# PFC_screen.net
KiCad netlist of a schematic drawn in EAGLE
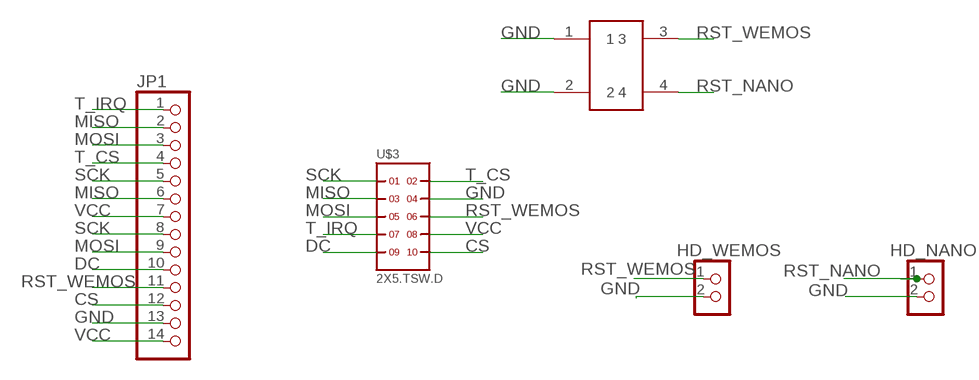
[diagram p0: schematic, sheet 1]

(export (version "E")
  (design (tool "Eeschema 10.0.6"))
  (components
    (comp (ref "HD_NANO")
      (value "PINHD-2X1")
      (footprint "eagle-import:2X01")
      (libsource (lib "eagle-import") (part "PINHD-2X1"))
    )
    (comp (ref "HD_WEMOS")
      (value "PINHD-2X1")
      (footprint "eagle-import:2X01")
      (libsource (lib "eagle-import") (part "PINHD-2X1"))
    )
    (comp (ref "JP1")
      (value "PINHD-1X14-CB")
      (footprint "eagle-import:1X14-CB")
      (libsource (lib "eagle-import") (part "PINHD-1X14-CB"))
    )
    (comp (ref "U$1")
      (value "EK1019")
      (footprint "eagle-import:EK1019_6X6X5MM")
      (libsource (lib "eagle-import") (part "EK1019"))
    )
    (comp (ref "U$3")
      (value "2X5.TSW.D")
      (footprint "eagle-import:TSW-105-XXX-D-XXX")
      (libsource (lib "eagle-import") (part "2X5.TSW.D"))
    )
  )
  (nets
    (net (code "1") (name "/CS") (class "Default")
      (node (ref "JP1") (pin "12") (pinfunction "12_12") (pintype "passive"))
      (node (ref "U$3") (pin "10") (pinfunction "10_10") (pintype "bidirectional"))
    )
    (net (code "2") (name "/DC") (class "Default")
      (node (ref "JP1") (pin "10") (pinfunction "10_10") (pintype "passive"))
      (node (ref "U$3") (pin "9") (pinfunction "9_9") (pintype "bidirectional"))
    )
    (net (code "3") (name "/GND") (class "Default")
      (node (ref "HD_NANO") (pin "2") (pinfunction "3_2") (pintype "passive"))
      (node (ref "HD_WEMOS") (pin "2") (pinfunction "3_2") (pintype "passive"))
      (node (ref "JP1") (pin "13") (pinfunction "13_13") (pintype "passive"))
      (node (ref "U$1") (pin "1") (pinfunction "1_1") (pintype "bidirectional"))
      (node (ref "U$1") (pin "2") (pinfunction "2_2") (pintype "bidirectional"))
      (node (ref "U$3") (pin "4") (pinfunction "4_4") (pintype "bidirectional"))
    )
    (net (code "4") (name "/MISO") (class "Default")
      (node (ref "JP1") (pin "2") (pinfunction "2_2") (pintype "passive"))
      (node (ref "JP1") (pin "6") (pinfunction "6_6") (pintype "passive"))
      (node (ref "U$3") (pin "3") (pinfunction "3_3") (pintype "bidirectional"))
    )
    (net (code "5") (name "/MOSI") (class "Default")
      (node (ref "JP1") (pin "3") (pinfunction "3_3") (pintype "passive"))
      (node (ref "JP1") (pin "9") (pinfunction "9_9") (pintype "passive"))
      (node (ref "U$3") (pin "5") (pinfunction "5_5") (pintype "bidirectional"))
    )
    (net (code "6") (name "/RST_NANO") (class "Default")
      (node (ref "HD_NANO") (pin "1") (pinfunction "1_1") (pintype "passive"))
      (node (ref "U$1") (pin "4") (pinfunction "4_4") (pintype "bidirectional"))
    )
    (net (code "7") (name "/RST_WEMOS") (class "Default")
      (node (ref "HD_WEMOS") (pin "1") (pinfunction "1_1") (pintype "passive"))
      (node (ref "JP1") (pin "11") (pinfunction "11_11") (pintype "passive"))
      (node (ref "U$1") (pin "3") (pinfunction "3_3") (pintype "bidirectional"))
      (node (ref "U$3") (pin "6") (pinfunction "6_6") (pintype "bidirectional"))
    )
    (net (code "8") (name "/SCK") (class "Default")
      (node (ref "JP1") (pin "5") (pinfunction "5_5") (pintype "passive"))
      (node (ref "JP1") (pin "8") (pinfunction "8_8") (pintype "passive"))
      (node (ref "U$3") (pin "1") (pinfunction "1_1") (pintype "bidirectional"))
    )
    (net (code "9") (name "/T_CS") (class "Default")
      (node (ref "JP1") (pin "4") (pinfunction "4_4") (pintype "passive"))
      (node (ref "U$3") (pin "2") (pinfunction "2_2") (pintype "bidirectional"))
    )
    (net (code "10") (name "/T_IRQ") (class "Default")
      (node (ref "JP1") (pin "1") (pinfunction "1_1") (pintype "passive"))
      (node (ref "U$3") (pin "7") (pinfunction "7_7") (pintype "bidirectional"))
    )
    (net (code "11") (name "/VCC") (class "Default")
      (node (ref "JP1") (pin "14") (pinfunction "14_14") (pintype "passive"))
      (node (ref "JP1") (pin "7") (pinfunction "7_7") (pintype "passive"))
      (node (ref "U$3") (pin "8") (pinfunction "8_8") (pintype "bidirectional"))
    )
  )
)
